# CAN-to-CAN.net
KiCad netlist of a schematic drawn in Altium Designer
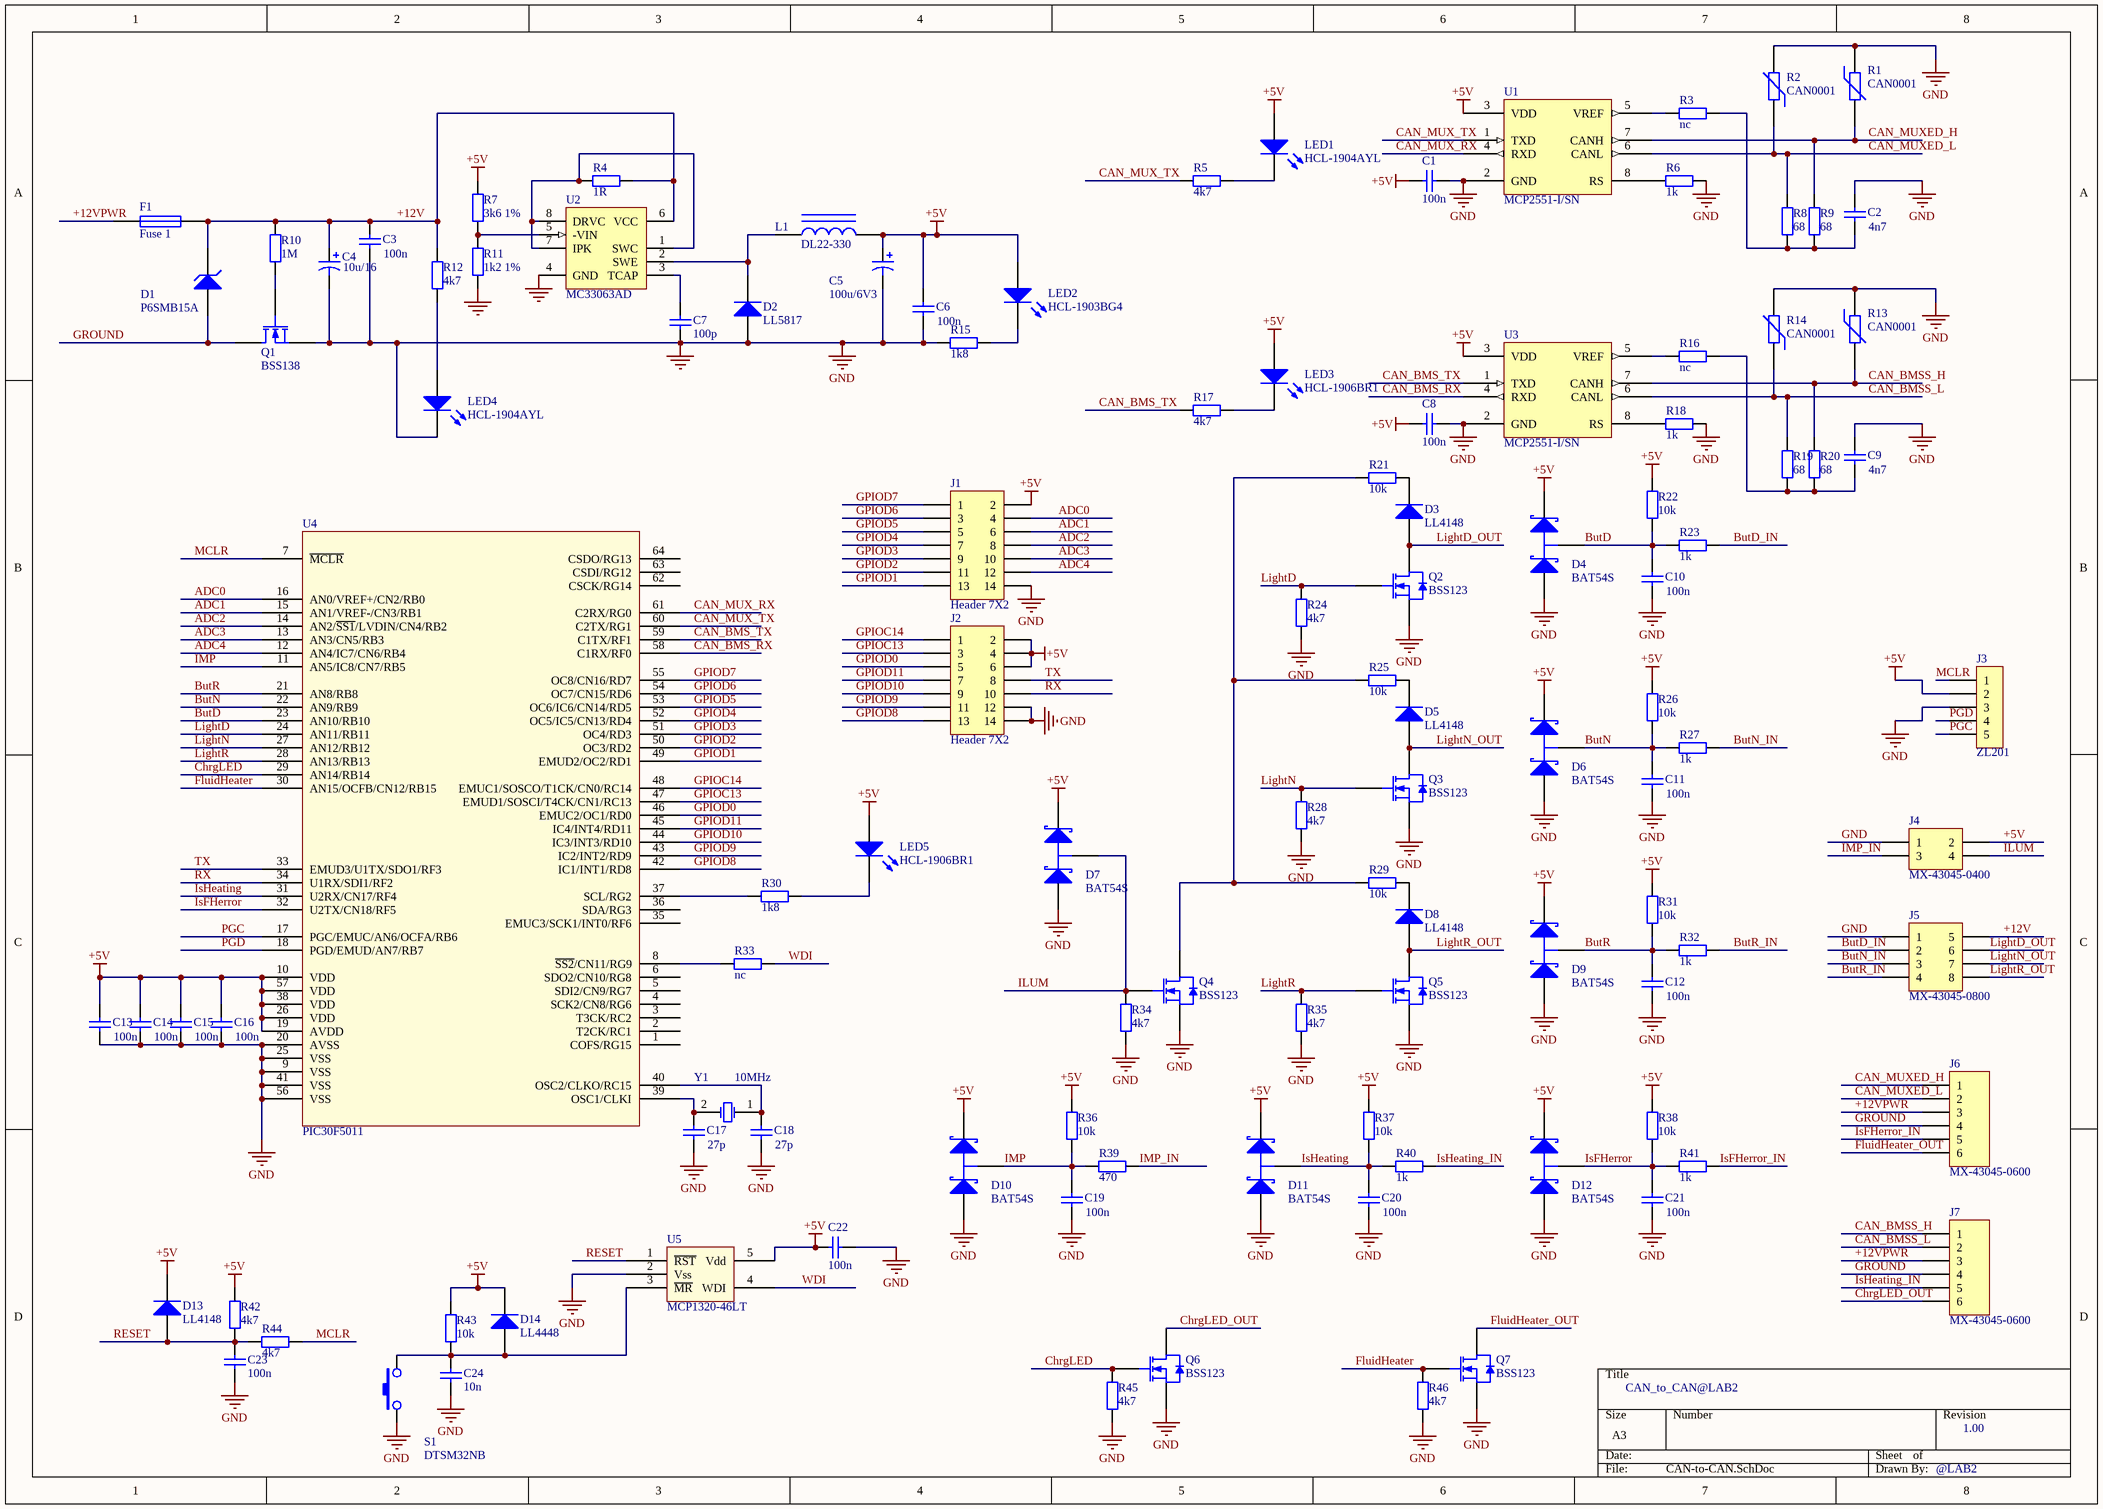
[diagram p0: CAN-to-CAN.SchDoc]

(export (version "E")
  (design (tool "Eeschema 10.0.6"))
  (components
    (comp (ref "C1")
      (value "100n")
      (footprint "0603")
      (description "Capacitor")
      (libsource (lib "Miscellaneous Devices") (part "Cap"))
    )
    (comp (ref "C2")
      (value "4n7")
      (footprint "0603")
      (description "Capacitor")
      (libsource (lib "Miscellaneous Devices") (part "Cap"))
    )
    (comp (ref "C3")
      (value "100n")
      (footprint "0402")
      (description "Capacitor")
      (libsource (lib "Miscellaneous Devices") (part "Cap"))
    )
    (comp (ref "C4")
      (value "10u/16")
      (footprint "0402")
      (description "Polarized Capacitor (Radial)")
      (libsource (lib "Miscellaneous Devices") (part "Cap Pol1"))
    )
    (comp (ref "C5")
      (value "100u/6V3")
      (footprint "0402")
      (description "Polarized Capacitor (Radial)")
      (libsource (lib "Miscellaneous Devices") (part "Cap Pol1"))
    )
    (comp (ref "C6")
      (value "100n")
      (footprint "0603")
      (description "Capacitor")
      (libsource (lib "Miscellaneous Devices") (part "Cap"))
    )
    (comp (ref "C7")
      (value "100p")
      (footprint "0603")
      (description "Capacitor")
      (libsource (lib "Miscellaneous Devices") (part "Cap"))
    )
    (comp (ref "C8")
      (value "100n")
      (footprint "0603")
      (description "Capacitor")
      (libsource (lib "Miscellaneous Devices") (part "Cap"))
    )
    (comp (ref "C9")
      (value "4n7")
      (footprint "0603")
      (description "Capacitor")
      (libsource (lib "Miscellaneous Devices") (part "Cap"))
    )
    (comp (ref "C10")
      (value "100n")
      (footprint "0603")
      (description "Capacitor")
      (libsource (lib "Miscellaneous Devices") (part "Cap"))
    )
    (comp (ref "C11")
      (value "100n")
      (footprint "0603")
      (description "Capacitor")
      (libsource (lib "Miscellaneous Devices") (part "Cap"))
    )
    (comp (ref "C12")
      (value "100n")
      (footprint "0603")
      (description "Capacitor")
      (libsource (lib "Miscellaneous Devices") (part "Cap"))
    )
    (comp (ref "C13")
      (value "100n")
      (footprint "0603")
      (description "Capacitor")
      (libsource (lib "Miscellaneous Devices") (part "Cap"))
    )
    (comp (ref "C14")
      (value "100n")
      (footprint "0603")
      (description "Capacitor")
      (libsource (lib "Miscellaneous Devices") (part "Cap"))
    )
    (comp (ref "C15")
      (value "100n")
      (footprint "0603")
      (description "Capacitor")
      (libsource (lib "Miscellaneous Devices") (part "Cap"))
    )
    (comp (ref "C16")
      (value "100n")
      (footprint "0603")
      (description "Capacitor")
      (libsource (lib "Miscellaneous Devices") (part "Cap"))
    )
    (comp (ref "C17")
      (value "27p")
      (footprint "0603")
      (description "Capacitor")
      (libsource (lib "Miscellaneous Devices") (part "Cap"))
    )
    (comp (ref "C18")
      (value "27p")
      (footprint "0603")
      (description "Capacitor")
      (libsource (lib "Miscellaneous Devices") (part "Cap"))
    )
    (comp (ref "C19")
      (value "100n")
      (footprint "0603")
      (description "Capacitor")
      (libsource (lib "Miscellaneous Devices") (part "Cap"))
    )
    (comp (ref "C20")
      (value "100n")
      (footprint "0603")
      (description "Capacitor")
      (libsource (lib "Miscellaneous Devices") (part "Cap"))
    )
    (comp (ref "C21")
      (value "100n")
      (footprint "0603")
      (description "Capacitor")
      (libsource (lib "Miscellaneous Devices") (part "Cap"))
    )
    (comp (ref "C22")
      (value "100n")
      (footprint "0603")
      (description "Capacitor")
      (libsource (lib "Miscellaneous Devices") (part "Cap"))
    )
    (comp (ref "C23")
      (value "100n")
      (footprint "0603")
      (description "Capacitor")
      (libsource (lib "Miscellaneous Devices") (part "Cap"))
    )
    (comp (ref "C24")
      (value "10n")
      (footprint "0603")
      (description "Capacitor")
      (libsource (lib "Miscellaneous Devices") (part "Cap"))
    )
    (comp (ref "D1")
      (value "P6SMB15A")
      (footprint "SMB")
      (description "Zener Diode")
      (libsource (lib "Miscellaneous Devices") (part "D Zener"))
    )
    (comp (ref "D2")
      (value "LL5817")
      (footprint "DIODE_SMC")
      (description "High Conductance Fast Diode")
      (libsource (lib "FSC Discrete Diode") (part "1N4148"))
    )
    (comp (ref "D3")
      (value "LL4148")
      (footprint "DIODE_SMC")
      (description "High Conductance Fast Diode")
      (libsource (lib "FSC Discrete Diode") (part "1N4148"))
    )
    (comp (ref "D4")
      (value "BAT54S")
      (footprint "SOT-23_M")
      (description "Schottky Barrier Double Diode")
      (libsource (lib "Philips Discrete Diode - Schottky") (part "BAT54S"))
    )
    (comp (ref "D5")
      (value "LL4148")
      (footprint "DIODE_SMC")
      (description "High Conductance Fast Diode")
      (libsource (lib "FSC Discrete Diode") (part "1N4148"))
    )
    (comp (ref "D6")
      (value "BAT54S")
      (footprint "SOT23_M")
      (description "Schottky Barrier Double Diode")
      (libsource (lib "Philips Discrete Diode - Schottky") (part "BAT54S"))
    )
    (comp (ref "D7")
      (value "BAT54S")
      (footprint "SOT23_M")
      (description "Schottky Barrier Double Diode")
      (libsource (lib "Philips Discrete Diode - Schottky") (part "BAT54S"))
    )
    (comp (ref "D8")
      (value "LL4148")
      (footprint "DIODE_SMC")
      (description "High Conductance Fast Diode")
      (libsource (lib "FSC Discrete Diode") (part "1N4148"))
    )
    (comp (ref "D9")
      (value "BAT54S")
      (footprint "SOT23_M")
      (description "Schottky Barrier Double Diode")
      (libsource (lib "Philips Discrete Diode - Schottky") (part "BAT54S"))
    )
    (comp (ref "D10")
      (value "BAT54S")
      (footprint "SOT23_M")
      (description "Schottky Barrier Double Diode")
      (libsource (lib "Philips Discrete Diode - Schottky") (part "BAT54S"))
    )
    (comp (ref "D11")
      (value "BAT54S")
      (footprint "SOT23_M")
      (description "Schottky Barrier Double Diode")
      (libsource (lib "Philips Discrete Diode - Schottky") (part "BAT54S"))
    )
    (comp (ref "D12")
      (value "BAT54S")
      (footprint "SOT23_M")
      (description "Schottky Barrier Double Diode")
      (libsource (lib "Philips Discrete Diode - Schottky") (part "BAT54S"))
    )
    (comp (ref "D13")
      (value "LL4148")
      (footprint "DIODE_SMC")
      (description "High Conductance Fast Diode")
      (libsource (lib "FSC Discrete Diode") (part "1N4148"))
    )
    (comp (ref "D14")
      (value "LL4448")
      (footprint "DIODE_SMC")
      (description "Default Diode")
      (libsource (lib "Miscellaneous Devices") (part "Diode"))
    )
    (comp (ref "F1")
      (value "Fuse 1")
      (footprint "1812")
      (description "Fuse")
      (libsource (lib "Miscellaneous Devices") (part "Fuse 1"))
    )
    (comp (ref "J1")
      (value "Header 7X2")
      (footprint "HDR2X7")
      (description "Header, 7-Pin, Dual row")
      (libsource (lib "Miscellaneous Connectors") (part "Header 7X2"))
    )
    (comp (ref "J2")
      (value "Header 7X2")
      (footprint "HDR2X7")
      (description "Header, 7-Pin, Dual row")
      (libsource (lib "Miscellaneous Connectors") (part "Header 7X2"))
    )
    (comp (ref "J3")
      (value "ZL201")
      (footprint "HDR1X5")
      (description "Connector")
      (libsource (lib "*") (part "CON5"))
    )
    (comp (ref "J4")
      (value "MX-43045-0400")
      (footprint "SOT-343_M")
      (description "Header, 2-Pin, Dual row")
      (libsource (lib "Miscellaneous Connectors") (part "Header 2X2"))
    )
    (comp (ref "J5")
      (value "MX-43045-0800")
      (footprint "DB008_M")
      (description "Header, 4-Pin, Dual row")
      (libsource (lib "Miscellaneous Connectors") (part "Header 4X2A"))
    )
    (comp (ref "J6")
      (value "MX-43045-0600")
      (footprint "Miscellaneous Connectors:HDR1X6")
      (description "Header, 6-Pin")
      (libsource (lib "Miscellaneous Connectors") (part "Header 6"))
    )
    (comp (ref "J7")
      (value "MX-43045-0600")
      (footprint "Miscellaneous Connectors:HDR1X6")
      (description "Header, 6-Pin")
      (libsource (lib "Miscellaneous Connectors") (part "Header 6"))
    )
    (comp (ref "L1")
      (value "DL22-330")
      (footprint "INDC1608L")
      (description "Magnetic-Core Inductor")
      (libsource (lib "Miscellaneous Devices") (part "Inductor Iron"))
    )
    (comp (ref "LED1")
      (value "HCL-1904AYL")
      (footprint "0603")
      (description "Typical BLUE SiC LED")
      (libsource (lib "Miscellaneous Devices") (part "LED3"))
    )
    (comp (ref "LED2")
      (value "HCL-1903BG4")
      (footprint "0603")
      (description "Typical BLUE SiC LED")
      (libsource (lib "Miscellaneous Devices") (part "LED3"))
    )
    (comp (ref "LED3")
      (value "HCL-1906BR1")
      (footprint "0603")
      (description "Typical BLUE SiC LED")
      (libsource (lib "Miscellaneous Devices") (part "LED3"))
    )
    (comp (ref "LED4")
      (value "HCL-1904AYL")
      (footprint "0603")
      (description "Typical BLUE SiC LED")
      (libsource (lib "Miscellaneous Devices") (part "LED3"))
    )
    (comp (ref "LED5")
      (value "HCL-1906BR1")
      (footprint "0603")
      (description "Typical BLUE SiC LED")
      (libsource (lib "Miscellaneous Devices") (part "LED3"))
    )
    (comp (ref "Q1")
      (value "BSS138")
      (footprint "SOT23_M")
      (description "N-Channel Enhancement Mode Vertical DMOS FET")
      (libsource (lib "Zetex Discrete MOSFET") (part "BSS138"))
    )
    (comp (ref "Q2")
      (value "BSS123")
      (footprint "SOT23_M")
      (description "N-channel Enhancement Mode Vertical D-MOSFET")
      (libsource (lib "Philips Discrete MOSFET - Low Power") (part "BSS123"))
    )
    (comp (ref "Q3")
      (value "BSS123")
      (footprint "SOT23_M")
      (description "N-channel Enhancement Mode Vertical D-MOSFET")
      (libsource (lib "Philips Discrete MOSFET - Low Power") (part "BSS123"))
    )
    (comp (ref "Q4")
      (value "BSS123")
      (footprint "SOT23_M")
      (description "N-channel Enhancement Mode Vertical D-MOSFET")
      (libsource (lib "Philips Discrete MOSFET - Low Power") (part "BSS123"))
    )
    (comp (ref "Q5")
      (value "BSS123")
      (footprint "SOT23_M")
      (description "N-channel Enhancement Mode Vertical D-MOSFET")
      (libsource (lib "Philips Discrete MOSFET - Low Power") (part "BSS123"))
    )
    (comp (ref "Q6")
      (value "BSS123")
      (footprint "SOT23_M")
      (description "N-channel Enhancement Mode Vertical D-MOSFET")
      (libsource (lib "Philips Discrete MOSFET - Low Power") (part "BSS123"))
    )
    (comp (ref "Q7")
      (value "BSS123")
      (footprint "SOT23_M")
      (description "N-channel Enhancement Mode Vertical D-MOSFET")
      (libsource (lib "Philips Discrete MOSFET - Low Power") (part "BSS123"))
    )
    (comp (ref "R1")
      (value "CAN0001")
      (footprint "0603")
      (description "Varistor (Voltage-Sensitive Resistor)")
      (libsource (lib "Miscellaneous Devices") (part "Res Varistor"))
    )
    (comp (ref "R2")
      (value "CAN0001")
      (footprint "0603")
      (description "Varistor (Voltage-Sensitive Resistor)")
      (libsource (lib "Miscellaneous Devices") (part "Res Varistor"))
    )
    (comp (ref "R3")
      (value "nc")
      (footprint "0603")
      (description "Resistor")
      (libsource (lib "") (part "Res2_1"))
    )
    (comp (ref "R4")
      (value "1R")
      (footprint "12Z-2010")
      (description "Resistor")
      (libsource (lib "") (part "Res2_1"))
    )
    (comp (ref "R5")
      (value "4k7")
      (footprint "0603")
      (description "Resistor")
      (libsource (lib "") (part "Res2_2"))
    )
    (comp (ref "R6")
      (value "1k")
      (footprint "0603")
      (description "Resistor")
      (libsource (lib "") (part "Res2_1"))
    )
    (comp (ref "R7")
      (value "3k6 1%")
      (footprint "0603")
      (description "Resistor")
      (libsource (lib "Miscellaneous Devices") (part "Res2"))
    )
    (comp (ref "R8")
      (value "68")
      (footprint "0603")
      (description "Resistor")
      (libsource (lib "Miscellaneous Devices") (part "Res2"))
    )
    (comp (ref "R9")
      (value "68")
      (footprint "0603")
      (description "Resistor")
      (libsource (lib "Miscellaneous Devices") (part "Res2"))
    )
    (comp (ref "R10")
      (value "1M")
      (footprint "0603")
      (description "Resistor")
      (libsource (lib "Miscellaneous Devices") (part "Res2"))
    )
    (comp (ref "R11")
      (value "1k2 1%")
      (footprint "0603")
      (description "Resistor")
      (libsource (lib "") (part "Res2_3"))
    )
    (comp (ref "R12")
      (value "4k7")
      (footprint "0603")
      (description "Resistor")
      (libsource (lib "Miscellaneous Devices") (part "Res2"))
    )
    (comp (ref "R13")
      (value "CAN0001")
      (footprint "0603")
      (description "Varistor (Voltage-Sensitive Resistor)")
      (libsource (lib "Miscellaneous Devices") (part "Res Varistor"))
    )
    (comp (ref "R14")
      (value "CAN0001")
      (footprint "0603")
      (description "Varistor (Voltage-Sensitive Resistor)")
      (libsource (lib "Miscellaneous Devices") (part "Res Varistor"))
    )
    (comp (ref "R15")
      (value "1k8")
      (footprint "0603")
      (description "Resistor")
      (libsource (lib "") (part "Res2_2"))
    )
    (comp (ref "R16")
      (value "nc")
      (footprint "0603")
      (description "Resistor")
      (libsource (lib "") (part "Res2_1"))
    )
    (comp (ref "R17")
      (value "4k7")
      (footprint "0603")
      (description "Resistor")
      (libsource (lib "") (part "Res2_2"))
    )
    (comp (ref "R18")
      (value "1k")
      (footprint "0603")
      (description "Resistor")
      (libsource (lib "") (part "Res2_1"))
    )
    (comp (ref "R19")
      (value "68")
      (footprint "0603")
      (description "Resistor")
      (libsource (lib "Miscellaneous Devices") (part "Res2"))
    )
    (comp (ref "R20")
      (value "68")
      (footprint "0603")
      (description "Resistor")
      (libsource (lib "Miscellaneous Devices") (part "Res2"))
    )
    (comp (ref "R21")
      (value "10k")
      (footprint "0603")
      (description "Resistor")
      (libsource (lib "") (part "Res2_1"))
    )
    (comp (ref "R22")
      (value "10k")
      (footprint "0603")
      (description "Resistor")
      (libsource (lib "Miscellaneous Devices") (part "Res2"))
    )
    (comp (ref "R23")
      (value "1k")
      (footprint "0603")
      (description "Resistor")
      (libsource (lib "") (part "Res2_2"))
    )
    (comp (ref "R24")
      (value "4k7")
      (footprint "0603")
      (description "Resistor")
      (libsource (lib "Miscellaneous Devices") (part "Res2"))
    )
    (comp (ref "R25")
      (value "10k")
      (footprint "0603")
      (description "Resistor")
      (libsource (lib "") (part "Res2_1"))
    )
    (comp (ref "R26")
      (value "10k")
      (footprint "0603")
      (description "Resistor")
      (libsource (lib "Miscellaneous Devices") (part "Res2"))
    )
    (comp (ref "R27")
      (value "1k")
      (footprint "0603")
      (description "Resistor")
      (libsource (lib "") (part "Res2_2"))
    )
    (comp (ref "R28")
      (value "4k7")
      (footprint "0603")
      (description "Resistor")
      (libsource (lib "Miscellaneous Devices") (part "Res2"))
    )
    (comp (ref "R29")
      (value "10k")
      (footprint "0603")
      (description "Resistor")
      (libsource (lib "") (part "Res2_1"))
    )
    (comp (ref "R30")
      (value "1k8")
      (footprint "0603")
      (description "Resistor")
      (libsource (lib "") (part "Res2_2"))
    )
    (comp (ref "R31")
      (value "10k")
      (footprint "0603")
      (description "Resistor")
      (libsource (lib "Miscellaneous Devices") (part "Res2"))
    )
    (comp (ref "R32")
      (value "1k")
      (footprint "0603")
      (description "Resistor")
      (libsource (lib "") (part "Res2_2"))
    )
    (comp (ref "R33")
      (value "nc")
      (footprint "0603")
      (description "Resistor")
      (libsource (lib "") (part "Res2_2"))
    )
    (comp (ref "R34")
      (value "4k7")
      (footprint "0603")
      (description "Resistor")
      (libsource (lib "Miscellaneous Devices") (part "Res2"))
    )
    (comp (ref "R35")
      (value "4k7")
      (footprint "0603")
      (description "Resistor")
      (libsource (lib "Miscellaneous Devices") (part "Res2"))
    )
    (comp (ref "R36")
      (value "10k")
      (footprint "0603")
      (description "Resistor")
      (libsource (lib "Miscellaneous Devices") (part "Res2"))
    )
    (comp (ref "R37")
      (value "10k")
      (footprint "0603")
      (description "Resistor")
      (libsource (lib "Miscellaneous Devices") (part "Res2"))
    )
    (comp (ref "R38")
      (value "10k")
      (footprint "0603")
      (description "Resistor")
      (libsource (lib "Miscellaneous Devices") (part "Res2"))
    )
    (comp (ref "R39")
      (value "470")
      (footprint "0603")
      (description "Resistor")
      (libsource (lib "") (part "Res2_2"))
    )
    (comp (ref "R40")
      (value "1k")
      (footprint "0603")
      (description "Resistor")
      (libsource (lib "") (part "Res2_2"))
    )
    (comp (ref "R41")
      (value "1k")
      (footprint "0603")
      (description "Resistor")
      (libsource (lib "") (part "Res2_2"))
    )
    (comp (ref "R42")
      (value "4k7")
      (footprint "0603")
      (description "Resistor")
      (libsource (lib "Miscellaneous Devices") (part "Res2"))
    )
    (comp (ref "R43")
      (value "10k")
      (footprint "0603")
      (description "Resistor")
      (libsource (lib "") (part "Res2_3"))
    )
    (comp (ref "R44")
      (value "4k7")
      (footprint "0603")
      (description "Resistor")
      (libsource (lib "") (part "Res2_2"))
    )
    (comp (ref "R45")
      (value "4k7")
      (footprint "0603")
      (description "Resistor")
      (libsource (lib "Miscellaneous Devices") (part "Res2"))
    )
    (comp (ref "R46")
      (value "4k7")
      (footprint "0603")
      (description "Resistor")
      (libsource (lib "Miscellaneous Devices") (part "Res2"))
    )
    (comp (ref "S1")
      (value "DTSM32NB")
      (footprint "SPST-2")
      (description "Switch PushButton")
      (libsource (lib "*") (part "PUSHB"))
    )
    (comp (ref "U1")
      (value "MCP2551-I/SN")
      (footprint "DB008_M")
      (description "High Speed CAN Transceiver, 8-Pin Plastic SOIC, Industrial Grade")
      (libsource (lib "Microchip Interface Line Transceiver") (part "MCP2551-I/SN"))
    )
    (comp (ref "U2")
      (value "MC33063AD")
      (footprint "SO8_N")
      (description "DC-to-DC Converter Control Circuit")
      (libsource (lib "Motorola Power Mgt DC-DC Converter") (part "MC33063AD"))
    )
    (comp (ref "U3")
      (value "MCP2551-I/SN")
      (footprint "M08A_L")
      (description "High Speed CAN Transceiver, 8-Pin Plastic SOIC, Industrial Grade")
      (libsource (lib "Microchip Interface Line Transceiver") (part "MCP2551-I/SN"))
    )
    (comp (ref "U4")
      (value "PIC30F5011")
      (footprint "RESC6332")
      (description "PIC30F5011 - Up")
      (libsource (lib "X-Tro's Misc") (part "PIC30F5011"))
    )
    (comp (ref "U5")
      (value "MCP1320-46LT")
      (footprint "SOT23-5")
      (libsource (lib "X-Tro's Misc") (part "MCP1320"))
    )
    (comp (ref "Y1")
      (value "10MHz")
      (footprint "XTALSMD2")
      (description "Crystal Oscillator")
      (libsource (lib "Miscellaneous Devices") (part "XTAL"))
    )
  )
  (nets
    (net (code "1") (name "+5V") (class "Default")
      (node (ref "C1") (pin "1") (pinfunction "1_1") (pintype "passive"))
      (node (ref "C13") (pin "1") (pinfunction "1_1") (pintype "passive"))
      (node (ref "C14") (pin "1") (pinfunction "1_1") (pintype "passive"))
      (node (ref "C15") (pin "1") (pinfunction "1_1") (pintype "passive"))
      (node (ref "C16") (pin "1") (pinfunction "1_1") (pintype "passive"))
      (node (ref "C22") (pin "1") (pinfunction "1_1") (pintype "passive"))
      (node (ref "C5") (pin "1") (pinfunction "1_1") (pintype "passive"))
      (node (ref "C6") (pin "1") (pinfunction "1_1") (pintype "passive"))
      (node (ref "C8") (pin "1") (pinfunction "1_1") (pintype "passive"))
      (node (ref "D10") (pin "2") (pinfunction "K_2") (pintype "passive"))
      (node (ref "D11") (pin "2") (pinfunction "K_2") (pintype "passive"))
      (node (ref "D12") (pin "2") (pinfunction "K_2") (pintype "passive"))
      (node (ref "D13") (pin "2") (pinfunction "K_2") (pintype "passive"))
      (node (ref "D14") (pin "2") (pinfunction "K_2") (pintype "passive"))
      (node (ref "D4") (pin "2") (pinfunction "K_2") (pintype "passive"))
      (node (ref "D6") (pin "2") (pinfunction "K_2") (pintype "passive"))
      (node (ref "D7") (pin "2") (pinfunction "K_2") (pintype "passive"))
      (node (ref "D9") (pin "2") (pinfunction "K_2") (pintype "passive"))
      (node (ref "J1") (pin "2") (pinfunction "2_2") (pintype "passive"))
      (node (ref "J2") (pin "2") (pinfunction "2_2") (pintype "passive"))
      (node (ref "J2") (pin "4") (pinfunction "4_4") (pintype "passive"))
      (node (ref "J2") (pin "6") (pinfunction "6_6") (pintype "passive"))
      (node (ref "J3") (pin "2") (pinfunction "2_2") (pintype "passive"))
      (node (ref "J4") (pin "2") (pinfunction "2_2") (pintype "passive"))
      (node (ref "L1") (pin "2") (pinfunction "2_2") (pintype "passive"))
      (node (ref "LED1") (pin "1") (pinfunction "A_1") (pintype "passive"))
      (node (ref "LED2") (pin "1") (pinfunction "A_1") (pintype "passive"))
      (node (ref "LED3") (pin "1") (pinfunction "A_1") (pintype "passive"))
      (node (ref "LED5") (pin "1") (pinfunction "A_1") (pintype "passive"))
      (node (ref "R22") (pin "1") (pinfunction "1_1") (pintype "passive"))
      (node (ref "R26") (pin "1") (pinfunction "1_1") (pintype "passive"))
      (node (ref "R31") (pin "1") (pinfunction "1_1") (pintype "passive"))
      (node (ref "R36") (pin "1") (pinfunction "1_1") (pintype "passive"))
      (node (ref "R37") (pin "1") (pinfunction "1_1") (pintype "passive"))
      (node (ref "R38") (pin "1") (pinfunction "1_1") (pintype "passive"))
      (node (ref "R42") (pin "1") (pinfunction "1_1") (pintype "passive"))
      (node (ref "R43") (pin "2") (pinfunction "2_2") (pintype "passive"))
      (node (ref "R7") (pin "1") (pinfunction "1_1") (pintype "passive"))
      (node (ref "U1") (pin "3") (pinfunction "VDD_3") (pintype "power_in"))
      (node (ref "U3") (pin "3") (pinfunction "VDD_3") (pintype "power_in"))
      (node (ref "U4") (pin "10") (pinfunction "VDD_10") (pintype "passive"))
      (node (ref "U4") (pin "19") (pinfunction "AVDD_19") (pintype "passive"))
      (node (ref "U4") (pin "26") (pinfunction "VDD_26") (pintype "passive"))
      (node (ref "U4") (pin "38") (pinfunction "VDD_38") (pintype "passive"))
      (node (ref "U4") (pin "57") (pinfunction "VDD_57") (pintype "passive"))
      (node (ref "U5") (pin "5") (pinfunction "Vdd_5") (pintype "passive"))
    )
    (net (code "2") (name "/+12V") (class "Default")
      (node (ref "C3") (pin "1") (pinfunction "1_1") (pintype "passive"))
      (node (ref "C4") (pin "1") (pinfunction "1_1") (pintype "passive"))
      (node (ref "D1") (pin "2") (pinfunction "K_2") (pintype "passive"))
      (node (ref "F1") (pin "2") (pinfunction "2_2") (pintype "passive"))
      (node (ref "J5") (pin "5") (pinfunction "5_5") (pintype "passive"))
      (node (ref "R10") (pin "1") (pinfunction "1_1") (pintype "passive"))
      (node (ref "R12") (pin "1") (pinfunction "1_1") (pintype "passive"))
      (node (ref "R4") (pin "2") (pinfunction "2_2") (pintype "passive"))
      (node (ref "U2") (pin "6") (pinfunction "VCC_6") (pintype "power_in"))
    )
    (net (code "3") (name "/+12VPWR") (class "Default")
      (node (ref "F1") (pin "1") (pinfunction "1_1") (pintype "passive"))
      (node (ref "J6") (pin "3") (pinfunction "3_3") (pintype "passive"))
      (node (ref "J7") (pin "3") (pinfunction "3_3") (pintype "passive"))
    )
    (net (code "4") (name "/ADC0") (class "Default")
      (node (ref "J1") (pin "4") (pinfunction "4_4") (pintype "passive"))
      (node (ref "U4") (pin "16") (pinfunction "AN0/VREF+/CN2/RB0_16") (pintype "passive"))
    )
    (net (code "5") (name "/ADC1") (class "Default")
      (node (ref "J1") (pin "6") (pinfunction "6_6") (pintype "passive"))
      (node (ref "U4") (pin "15") (pinfunction "AN1/VREF-/CN3/RB1_15") (pintype "passive"))
    )
    (net (code "6") (name "/ADC2") (class "Default")
      (node (ref "J1") (pin "8") (pinfunction "8_8") (pintype "passive"))
      (node (ref "U4") (pin "14") (pinfunction "AN2/~{SS1}/LVDIN/CN4/RB2_14") (pintype "passive"))
    )
    (net (code "7") (name "/ADC3") (class "Default")
      (node (ref "J1") (pin "10") (pinfunction "10_10") (pintype "passive"))
      (node (ref "U4") (pin "13") (pinfunction "AN3/CN5/RB3_13") (pintype "passive"))
    )
    (net (code "8") (name "/ADC4") (class "Default")
      (node (ref "J1") (pin "12") (pinfunction "12_12") (pintype "passive"))
      (node (ref "U4") (pin "12") (pinfunction "AN4/IC7/CN6/RB4_12") (pintype "passive"))
    )
    (net (code "9") (name "/ButD") (class "Default")
      (node (ref "C10") (pin "1") (pinfunction "1_1") (pintype "passive"))
      (node (ref "D4") (pin "3") (pinfunction "C_3") (pintype "passive"))
      (node (ref "R22") (pin "2") (pinfunction "2_2") (pintype "passive"))
      (node (ref "R23") (pin "2") (pinfunction "2_2") (pintype "passive"))
      (node (ref "U4") (pin "23") (pinfunction "AN10/RB10_23") (pintype "passive"))
    )
    (net (code "10") (name "/ButD_IN") (class "Default")
      (node (ref "J5") (pin "2") (pinfunction "2_2") (pintype "passive"))
      (node (ref "R23") (pin "1") (pinfunction "1_1") (pintype "passive"))
    )
    (net (code "11") (name "/ButN") (class "Default")
      (node (ref "C11") (pin "1") (pinfunction "1_1") (pintype "passive"))
      (node (ref "D6") (pin "3") (pinfunction "C_3") (pintype "passive"))
      (node (ref "R26") (pin "2") (pinfunction "2_2") (pintype "passive"))
      (node (ref "R27") (pin "2") (pinfunction "2_2") (pintype "passive"))
      (node (ref "U4") (pin "22") (pinfunction "AN9/RB9_22") (pintype "passive"))
    )
    (net (code "12") (name "/ButN_IN") (class "Default")
      (node (ref "J5") (pin "3") (pinfunction "3_3") (pintype "passive"))
      (node (ref "R27") (pin "1") (pinfunction "1_1") (pintype "passive"))
    )
    (net (code "13") (name "/ButR") (class "Default")
      (node (ref "C12") (pin "1") (pinfunction "1_1") (pintype "passive"))
      (node (ref "D9") (pin "3") (pinfunction "C_3") (pintype "passive"))
      (node (ref "R31") (pin "2") (pinfunction "2_2") (pintype "passive"))
      (node (ref "R32") (pin "2") (pinfunction "2_2") (pintype "passive"))
      (node (ref "U4") (pin "21") (pinfunction "AN8/RB8_21") (pintype "passive"))
    )
    (net (code "14") (name "/ButR_IN") (class "Default")
      (node (ref "J5") (pin "4") (pinfunction "4_4") (pintype "passive"))
      (node (ref "R32") (pin "1") (pinfunction "1_1") (pintype "passive"))
    )
    (net (code "15") (name "/CAN_BMSS_H") (class "Default")
      (node (ref "J7") (pin "1") (pinfunction "1_1") (pintype "passive"))
      (node (ref "R13") (pin "2") (pinfunction "2_2") (pintype "passive"))
      (node (ref "R20") (pin "1") (pinfunction "1_1") (pintype "passive"))
      (node (ref "U3") (pin "7") (pinfunction "CANH_7") (pintype "output"))
    )
    (net (code "16") (name "/CAN_BMSS_L") (class "Default")
      (node (ref "J7") (pin "2") (pinfunction "2_2") (pintype "passive"))
      (node (ref "R14") (pin "1") (pinfunction "1_1") (pintype "passive"))
      (node (ref "R19") (pin "1") (pinfunction "1_1") (pintype "passive"))
      (node (ref "U3") (pin "6") (pinfunction "CANL_6") (pintype "output"))
    )
    (net (code "17") (name "/CAN_BMS_RX") (class "Default")
      (node (ref "U3") (pin "4") (pinfunction "RXD_4") (pintype "output"))
      (node (ref "U4") (pin "58") (pinfunction "C1RX/RF0_58") (pintype "passive"))
    )
    (net (code "18") (name "/CAN_BMS_TX") (class "Default")
      (node (ref "R17") (pin "2") (pinfunction "2_2") (pintype "passive"))
      (node (ref "U3") (pin "1") (pinfunction "TXD_1") (pintype "input"))
      (node (ref "U4") (pin "59") (pinfunction "C1TX/RF1_59") (pintype "passive"))
    )
    (net (code "19") (name "/CAN_MUXED_H") (class "Default")
      (node (ref "J6") (pin "1") (pinfunction "1_1") (pintype "passive"))
      (node (ref "R1") (pin "2") (pinfunction "2_2") (pintype "passive"))
      (node (ref "R9") (pin "1") (pinfunction "1_1") (pintype "passive"))
      (node (ref "U1") (pin "7") (pinfunction "CANH_7") (pintype "output"))
    )
    (net (code "20") (name "/CAN_MUXED_L") (class "Default")
      (node (ref "J6") (pin "2") (pinfunction "2_2") (pintype "passive"))
      (node (ref "R2") (pin "1") (pinfunction "1_1") (pintype "passive"))
      (node (ref "R8") (pin "1") (pinfunction "1_1") (pintype "passive"))
      (node (ref "U1") (pin "6") (pinfunction "CANL_6") (pintype "output"))
    )
    (net (code "21") (name "/CAN_MUX_RX") (class "Default")
      (node (ref "U1") (pin "4") (pinfunction "RXD_4") (pintype "output"))
      (node (ref "U4") (pin "61") (pinfunction "C2RX/RG0_61") (pintype "passive"))
    )
    (net (code "22") (name "/CAN_MUX_TX") (class "Default")
      (node (ref "R5") (pin "2") (pinfunction "2_2") (pintype "passive"))
      (node (ref "U1") (pin "1") (pinfunction "TXD_1") (pintype "input"))
      (node (ref "U4") (pin "60") (pinfunction "C2TX/RG1_60") (pintype "passive"))
    )
    (net (code "23") (name "/ChrgLED") (class "Default")
      (node (ref "Q6") (pin "3") (pinfunction "G_3") (pintype "passive"))
      (node (ref "R45") (pin "1") (pinfunction "1_1") (pintype "passive"))
      (node (ref "U4") (pin "29") (pinfunction "AN14/RB14_29") (pintype "passive"))
    )
    (net (code "24") (name "/ChrgLED_OUT") (class "Default")
      (node (ref "J7") (pin "6") (pinfunction "6_6") (pintype "passive"))
      (node (ref "Q6") (pin "1") (pinfunction "D_1") (pintype "passive"))
    )
    (net (code "25") (name "/FluidHeater") (class "Default")
      (node (ref "Q7") (pin "3") (pinfunction "G_3") (pintype "passive"))
      (node (ref "R46") (pin "1") (pinfunction "1_1") (pintype "passive"))
      (node (ref "U4") (pin "30") (pinfunction "AN15/OCFB/CN12/RB15_30") (pintype "passive"))
    )
    (net (code "26") (name "/FluidHeater_OUT") (class "Default")
      (node (ref "J6") (pin "6") (pinfunction "6_6") (pintype "passive"))
      (node (ref "Q7") (pin "1") (pinfunction "D_1") (pintype "passive"))
    )
    (net (code "27") (name "/GPIOC13") (class "Default")
      (node (ref "J2") (pin "3") (pinfunction "3_3") (pintype "passive"))
      (node (ref "U4") (pin "47") (pinfunction "EMUD1/SOSCI/T4CK/CN1/RC13_47") (pintype "passive"))
    )
    (net (code "28") (name "/GPIOC14") (class "Default")
      (node (ref "J2") (pin "1") (pinfunction "1_1") (pintype "passive"))
      (node (ref "U4") (pin "48") (pinfunction "EMUC1/SOSCO/T1CK/CN0/RC14_48") (pintype "passive"))
    )
    (net (code "29") (name "/GPIOD0") (class "Default")
      (node (ref "J2") (pin "5") (pinfunction "5_5") (pintype "passive"))
      (node (ref "U4") (pin "46") (pinfunction "EMUC2/OC1/RD0_46") (pintype "passive"))
    )
    (net (code "30") (name "/GPIOD1") (class "Default")
      (node (ref "J1") (pin "13") (pinfunction "13_13") (pintype "passive"))
      (node (ref "U4") (pin "49") (pinfunction "EMUD2/OC2/RD1_49") (pintype "passive"))
    )
    (net (code "31") (name "/GPIOD2") (class "Default")
      (node (ref "J1") (pin "11") (pinfunction "11_11") (pintype "passive"))
      (node (ref "U4") (pin "50") (pinfunction "OC3/RD2_50") (pintype "passive"))
    )
    (net (code "32") (name "/GPIOD3") (class "Default")
      (node (ref "J1") (pin "9") (pinfunction "9_9") (pintype "passive"))
      (node (ref "U4") (pin "51") (pinfunction "OC4/RD3_51") (pintype "passive"))
    )
    (net (code "33") (name "/GPIOD4") (class "Default")
      (node (ref "J1") (pin "7") (pinfunction "7_7") (pintype "passive"))
      (node (ref "U4") (pin "52") (pinfunction "OC5/IC5/CN13/RD4_52") (pintype "passive"))
    )
    (net (code "34") (name "/GPIOD5") (class "Default")
      (node (ref "J1") (pin "5") (pinfunction "5_5") (pintype "passive"))
      (node (ref "U4") (pin "53") (pinfunction "OC6/IC6/CN14/RD5_53") (pintype "passive"))
    )
    (net (code "35") (name "/GPIOD6") (class "Default")
      (node (ref "J1") (pin "3") (pinfunction "3_3") (pintype "passive"))
      (node (ref "U4") (pin "54") (pinfunction "OC7/CN15/RD6_54") (pintype "passive"))
    )
    (net (code "36") (name "/GPIOD7") (class "Default")
      (node (ref "J1") (pin "1") (pinfunction "1_1") (pintype "passive"))
      (node (ref "U4") (pin "55") (pinfunction "OC8/CN16/RD7_55") (pintype "passive"))
    )
    (net (code "37") (name "/GPIOD8") (class "Default")
      (node (ref "J2") (pin "13") (pinfunction "13_13") (pintype "passive"))
      (node (ref "U4") (pin "42") (pinfunction "IC1/INT1/RD8_42") (pintype "passive"))
    )
    (net (code "38") (name "/GPIOD9") (class "Default")
      (node (ref "J2") (pin "11") (pinfunction "11_11") (pintype "passive"))
      (node (ref "U4") (pin "43") (pinfunction "IC2/INT2/RD9_43") (pintype "passive"))
    )
    (net (code "39") (name "/GPIOD10") (class "Default")
      (node (ref "J2") (pin "9") (pinfunction "9_9") (pintype "passive"))
      (node (ref "U4") (pin "44") (pinfunction "IC3/INT3/RD10_44") (pintype "passive"))
    )
    (net (code "40") (name "/GPIOD11") (class "Default")
      (node (ref "J2") (pin "7") (pinfunction "7_7") (pintype "passive"))
      (node (ref "U4") (pin "45") (pinfunction "IC4/INT4/RD11_45") (pintype "passive"))
    )
    (net (code "41") (name "/GROUND") (class "Default")
      (node (ref "D1") (pin "1") (pinfunction "A_1") (pintype "passive"))
      (node (ref "J6") (pin "4") (pinfunction "4_4") (pintype "passive"))
      (node (ref "J7") (pin "4") (pinfunction "4_4") (pintype "passive"))
      (node (ref "Q1") (pin "1") (pinfunction "D_1") (pintype "passive"))
    )
    (net (code "42") (name "/ILUM") (class "Default")
      (node (ref "D7") (pin "3") (pinfunction "C_3") (pintype "passive"))
      (node (ref "J4") (pin "4") (pinfunction "4_4") (pintype "passive"))
      (node (ref "Q4") (pin "3") (pinfunction "G_3") (pintype "passive"))
      (node (ref "R34") (pin "1") (pinfunction "1_1") (pintype "passive"))
    )
    (net (code "43") (name "/IMP") (class "Default")
      (node (ref "C19") (pin "1") (pinfunction "1_1") (pintype "passive"))
      (node (ref "D10") (pin "3") (pinfunction "C_3") (pintype "passive"))
      (node (ref "R36") (pin "2") (pinfunction "2_2") (pintype "passive"))
      (node (ref "R39") (pin "2") (pinfunction "2_2") (pintype "passive"))
      (node (ref "U4") (pin "11") (pinfunction "AN5/IC8/CN7/RB5_11") (pintype "passive"))
    )
    (net (code "44") (name "/IMP_IN") (class "Default")
      (node (ref "J4") (pin "3") (pinfunction "3_3") (pintype "passive"))
      (node (ref "R39") (pin "1") (pinfunction "1_1") (pintype "passive"))
    )
    (net (code "45") (name "/IsFHerror") (class "Default")
      (node (ref "C21") (pin "1") (pinfunction "1_1") (pintype "passive"))
      (node (ref "D12") (pin "3") (pinfunction "C_3") (pintype "passive"))
      (node (ref "R38") (pin "2") (pinfunction "2_2") (pintype "passive"))
      (node (ref "R41") (pin "2") (pinfunction "2_2") (pintype "passive"))
      (node (ref "U4") (pin "32") (pinfunction "U2TX/CN18/RF5_32") (pintype "passive"))
    )
    (net (code "46") (name "/IsFHerror_IN") (class "Default")
      (node (ref "J6") (pin "5") (pinfunction "5_5") (pintype "passive"))
      (node (ref "R41") (pin "1") (pinfunction "1_1") (pintype "passive"))
    )
    (net (code "47") (name "/IsHeating") (class "Default")
      (node (ref "C20") (pin "1") (pinfunction "1_1") (pintype "passive"))
      (node (ref "D11") (pin "3") (pinfunction "C_3") (pintype "passive"))
      (node (ref "R37") (pin "2") (pinfunction "2_2") (pintype "passive"))
      (node (ref "R40") (pin "2") (pinfunction "2_2") (pintype "passive"))
      (node (ref "U4") (pin "31") (pinfunction "U2RX/CN17/RF4_31") (pintype "passive"))
    )
    (net (code "48") (name "/IsHeating_IN") (class "Default")
      (node (ref "J7") (pin "5") (pinfunction "5_5") (pintype "passive"))
      (node (ref "R40") (pin "1") (pinfunction "1_1") (pintype "passive"))
    )
    (net (code "49") (name "/LightD") (class "Default")
      (node (ref "Q2") (pin "3") (pinfunction "G_3") (pintype "passive"))
      (node (ref "R24") (pin "1") (pinfunction "1_1") (pintype "passive"))
      (node (ref "U4") (pin "24") (pinfunction "AN11/RB11_24") (pintype "passive"))
    )
    (net (code "50") (name "/LightD_OUT") (class "Default")
      (node (ref "D3") (pin "1") (pinfunction "A_1") (pintype "passive"))
      (node (ref "J5") (pin "6") (pinfunction "6_6") (pintype "passive"))
      (node (ref "Q2") (pin "1") (pinfunction "D_1") (pintype "passive"))
    )
    (net (code "51") (name "/LightN") (class "Default")
      (node (ref "Q3") (pin "3") (pinfunction "G_3") (pintype "passive"))
      (node (ref "R28") (pin "1") (pinfunction "1_1") (pintype "passive"))
      (node (ref "U4") (pin "27") (pinfunction "AN12/RB12_27") (pintype "passive"))
    )
    (net (code "52") (name "/LightN_OUT") (class "Default")
      (node (ref "D5") (pin "1") (pinfunction "A_1") (pintype "passive"))
      (node (ref "J5") (pin "7") (pinfunction "7_7") (pintype "passive"))
      (node (ref "Q3") (pin "1") (pinfunction "D_1") (pintype "passive"))
    )
    (net (code "53") (name "/LightR") (class "Default")
      (node (ref "Q5") (pin "3") (pinfunction "G_3") (pintype "passive"))
      (node (ref "R35") (pin "1") (pinfunction "1_1") (pintype "passive"))
      (node (ref "U4") (pin "28") (pinfunction "AN13/RB13_28") (pintype "passive"))
    )
    (net (code "54") (name "/LightR_OUT") (class "Default")
      (node (ref "D8") (pin "1") (pinfunction "A_1") (pintype "passive"))
      (node (ref "J5") (pin "8") (pinfunction "8_8") (pintype "passive"))
      (node (ref "Q5") (pin "1") (pinfunction "D_1") (pintype "passive"))
    )
    (net (code "55") (name "/MCLR") (class "Default")
      (node (ref "J3") (pin "1") (pinfunction "1_1") (pintype "passive"))
      (node (ref "R44") (pin "1") (pinfunction "1_1") (pintype "passive"))
      (node (ref "U4") (pin "7") (pinfunction "~{MCLR}_7") (pintype "passive"))
    )
    (net (code "56") (name "/PGC") (class "Default")
      (node (ref "J3") (pin "5") (pinfunction "5_5") (pintype "passive"))
      (node (ref "U4") (pin "17") (pinfunction "PGC/EMUC/AN6/OCFA/RB6_17") (pintype "passive"))
    )
    (net (code "57") (name "/PGD") (class "Default")
      (node (ref "J3") (pin "4") (pinfunction "4_4") (pintype "passive"))
      (node (ref "U4") (pin "18") (pinfunction "PGD/EMUD/AN7/RB7_18") (pintype "passive"))
    )
    (net (code "58") (name "/RESET") (class "Default")
      (node (ref "C23") (pin "2") (pinfunction "2_2") (pintype "passive"))
      (node (ref "D13") (pin "1") (pinfunction "A_1") (pintype "passive"))
      (node (ref "R42") (pin "2") (pinfunction "2_2") (pintype "passive"))
      (node (ref "R44") (pin "2") (pinfunction "2_2") (pintype "passive"))
      (node (ref "U5") (pin "1") (pinfunction "~{RST}_1") (pintype "passive"))
    )
    (net (code "59") (name "/RX") (class "Default")
      (node (ref "J2") (pin "10") (pinfunction "10_10") (pintype "passive"))
      (node (ref "U4") (pin "34") (pinfunction "U1RX/SDI1/RF2_34") (pintype "passive"))
    )
    (net (code "60") (name "/TX") (class "Default")
      (node (ref "J2") (pin "8") (pinfunction "8_8") (pintype "passive"))
      (node (ref "U4") (pin "33") (pinfunction "EMUD3/U1TX/SDO1/RF3_33") (pintype "passive"))
    )
    (net (code "61") (name "/WDI") (class "Default")
      (node (ref "R33") (pin "1") (pinfunction "1_1") (pintype "passive"))
      (node (ref "U5") (pin "4") (pinfunction "WDI_4") (pintype "passive"))
    )
    (net (code "62") (name "GND") (class "Default")
      (node (ref "C1") (pin "2") (pinfunction "2_2") (pintype "passive"))
      (node (ref "C10") (pin "2") (pinfunction "2_2") (pintype "passive"))
      (node (ref "C11") (pin "2") (pinfunction "2_2") (pintype "passive"))
      (node (ref "C12") (pin "2") (pinfunction "2_2") (pintype "passive"))
      (node (ref "C13") (pin "2") (pinfunction "2_2") (pintype "passive"))
      (node (ref "C14") (pin "2") (pinfunction "2_2") (pintype "passive"))
      (node (ref "C15") (pin "2") (pinfunction "2_2") (pintype "passive"))
      (node (ref "C16") (pin "2") (pinfunction "2_2") (pintype "passive"))
      (node (ref "C17") (pin "2") (pinfunction "2_2") (pintype "passive"))
      (node (ref "C18") (pin "2") (pinfunction "2_2") (pintype "passive"))
      (node (ref "C19") (pin "2") (pinfunction "2_2") (pintype "passive"))
      (node (ref "C2") (pin "1") (pinfunction "1_1") (pintype "passive"))
      (node (ref "C20") (pin "2") (pinfunction "2_2") (pintype "passive"))
      (node (ref "C21") (pin "2") (pinfunction "2_2") (pintype "passive"))
      (node (ref "C22") (pin "2") (pinfunction "2_2") (pintype "passive"))
      (node (ref "C23") (pin "1") (pinfunction "1_1") (pintype "passive"))
      (node (ref "C24") (pin "1") (pinfunction "1_1") (pintype "passive"))
      (node (ref "C3") (pin "2") (pinfunction "2_2") (pintype "passive"))
      (node (ref "C4") (pin "2") (pinfunction "2_2") (pintype "passive"))
      (node (ref "C5") (pin "2") (pinfunction "2_2") (pintype "passive"))
      (node (ref "C6") (pin "2") (pinfunction "2_2") (pintype "passive"))
      (node (ref "C7") (pin "1") (pinfunction "1_1") (pintype "passive"))
      (node (ref "C8") (pin "2") (pinfunction "2_2") (pintype "passive"))
      (node (ref "C9") (pin "1") (pinfunction "1_1") (pintype "passive"))
      (node (ref "D10") (pin "1") (pinfunction "A_1") (pintype "passive"))
      (node (ref "D11") (pin "1") (pinfunction "A_1") (pintype "passive"))
      (node (ref "D12") (pin "1") (pinfunction "A_1") (pintype "passive"))
      (node (ref "D2") (pin "1") (pinfunction "A_1") (pintype "passive"))
      (node (ref "D4") (pin "1") (pinfunction "A_1") (pintype "passive"))
      (node (ref "D6") (pin "1") (pinfunction "A_1") (pintype "passive"))
      (node (ref "D7") (pin "1") (pinfunction "A_1") (pintype "passive"))
      (node (ref "D9") (pin "1") (pinfunction "A_1") (pintype "passive"))
      (node (ref "J1") (pin "14") (pinfunction "14_14") (pintype "passive"))
      (node (ref "J2") (pin "12") (pinfunction "12_12") (pintype "passive"))
      (node (ref "J2") (pin "14") (pinfunction "14_14") (pintype "passive"))
      (node (ref "J3") (pin "3") (pinfunction "3_3") (pintype "passive"))
      (node (ref "J4") (pin "1") (pinfunction "1_1") (pintype "passive"))
      (node (ref "J5") (pin "1") (pinfunction "1_1") (pintype "passive"))
      (node (ref "LED4") (pin "2") (pinfunction "K_2") (pintype "passive"))
      (node (ref "Q1") (pin "2") (pinfunction "S_2") (pintype "passive"))
      (node (ref "Q2") (pin "2") (pinfunction "S_2") (pintype "passive"))
      (node (ref "Q3") (pin "2") (pinfunction "S_2") (pintype "passive"))
      (node (ref "Q4") (pin "2") (pinfunction "S_2") (pintype "passive"))
      (node (ref "Q5") (pin "2") (pinfunction "S_2") (pintype "passive"))
      (node (ref "Q6") (pin "2") (pinfunction "S_2") (pintype "passive"))
      (node (ref "Q7") (pin "2") (pinfunction "S_2") (pintype "passive"))
      (node (ref "R1") (pin "1") (pinfunction "1_1") (pintype "passive"))
      (node (ref "R11") (pin "1") (pinfunction "1_1") (pintype "passive"))
      (node (ref "R13") (pin "1") (pinfunction "1_1") (pintype "passive"))
      (node (ref "R14") (pin "2") (pinfunction "2_2") (pintype "passive"))
      (node (ref "R15") (pin "2") (pinfunction "2_2") (pintype "passive"))
      (node (ref "R18") (pin "2") (pinfunction "2_2") (pintype "passive"))
      (node (ref "R2") (pin "2") (pinfunction "2_2") (pintype "passive"))
      (node (ref "R24") (pin "2") (pinfunction "2_2") (pintype "passive"))
      (node (ref "R28") (pin "2") (pinfunction "2_2") (pintype "passive"))
      (node (ref "R34") (pin "2") (pinfunction "2_2") (pintype "passive"))
      (node (ref "R35") (pin "2") (pinfunction "2_2") (pintype "passive"))
      (node (ref "R45") (pin "2") (pinfunction "2_2") (pintype "passive"))
      (node (ref "R46") (pin "2") (pinfunction "2_2") (pintype "passive"))
      (node (ref "R6") (pin "2") (pinfunction "2_2") (pintype "passive"))
      (node (ref "S1") (pin "1") (pintype "passive"))
      (node (ref "U1") (pin "2") (pinfunction "GND_2") (pintype "power_in"))
      (node (ref "U2") (pin "4") (pinfunction "GND_4") (pintype "power_in"))
      (node (ref "U3") (pin "2") (pinfunction "GND_2") (pintype "power_in"))
      (node (ref "U4") (pin "20") (pinfunction "AVSS_20") (pintype "passive"))
      (node (ref "U4") (pin "25") (pinfunction "VSS_25") (pintype "passive"))
      (node (ref "U4") (pin "41") (pinfunction "VSS_41") (pintype "passive"))
      (node (ref "U4") (pin "56") (pinfunction "VSS_56") (pintype "passive"))
      (node (ref "U4") (pin "9") (pinfunction "VSS_9") (pintype "passive"))
      (node (ref "U5") (pin "2") (pinfunction "Vss_2") (pintype "passive"))
    )
    (net (code "63") (name "Net-(C2-Pad2)") (class "Default")
      (node (ref "C2") (pin "2") (pinfunction "2_2") (pintype "passive"))
      (node (ref "R3") (pin "2") (pinfunction "2_2") (pintype "passive"))
      (node (ref "R8") (pin "2") (pinfunction "2_2") (pintype "passive"))
      (node (ref "R9") (pin "2") (pinfunction "2_2") (pintype "passive"))
    )
    (net (code "64") (name "Net-(C9-Pad2)") (class "Default")
      (node (ref "C9") (pin "2") (pinfunction "2_2") (pintype "passive"))
      (node (ref "R16") (pin "2") (pinfunction "2_2") (pintype "passive"))
      (node (ref "R19") (pin "2") (pinfunction "2_2") (pintype "passive"))
      (node (ref "R20") (pin "2") (pinfunction "2_2") (pintype "passive"))
    )
    (net (code "65") (name "Net-(D2-K)") (class "Default")
      (node (ref "D2") (pin "2") (pinfunction "K_2") (pintype "passive"))
      (node (ref "L1") (pin "1") (pinfunction "1_1") (pintype "passive"))
      (node (ref "U2") (pin "2") (pinfunction "SWE_2") (pintype "open_emitter"))
    )
    (net (code "66") (name "Net-(D3-K)") (class "Default")
      (node (ref "D3") (pin "2") (pinfunction "K_2") (pintype "passive"))
      (node (ref "R21") (pin "2") (pinfunction "2_2") (pintype "passive"))
    )
    (net (code "67") (name "Net-(D5-K)") (class "Default")
      (node (ref "D5") (pin "2") (pinfunction "K_2") (pintype "passive"))
      (node (ref "R25") (pin "2") (pinfunction "2_2") (pintype "passive"))
    )
    (net (code "68") (name "Net-(D8-K)") (class "Default")
      (node (ref "D8") (pin "2") (pinfunction "K_2") (pintype "passive"))
      (node (ref "R29") (pin "2") (pinfunction "2_2") (pintype "passive"))
    )
    (net (code "69") (name "Net-(D14-A)") (class "Default")
      (node (ref "C24") (pin "2") (pinfunction "2_2") (pintype "passive"))
      (node (ref "D14") (pin "1") (pinfunction "A_1") (pintype "passive"))
      (node (ref "R43") (pin "1") (pinfunction "1_1") (pintype "passive"))
      (node (ref "S1") (pin "2") (pintype "passive"))
      (node (ref "U5") (pin "3") (pinfunction "~{MR}_3") (pintype "passive"))
    )
    (net (code "70") (name "Net-(LED1-K)") (class "Default")
      (node (ref "LED1") (pin "2") (pinfunction "K_2") (pintype "passive"))
      (node (ref "R5") (pin "1") (pinfunction "1_1") (pintype "passive"))
    )
    (net (code "71") (name "Net-(LED2-K)") (class "Default")
      (node (ref "LED2") (pin "2") (pinfunction "K_2") (pintype "passive"))
      (node (ref "R15") (pin "1") (pinfunction "1_1") (pintype "passive"))
    )
    (net (code "72") (name "Net-(LED3-K)") (class "Default")
      (node (ref "LED3") (pin "2") (pinfunction "K_2") (pintype "passive"))
      (node (ref "R17") (pin "1") (pinfunction "1_1") (pintype "passive"))
    )
    (net (code "73") (name "Net-(LED4-A)") (class "Default")
      (node (ref "LED4") (pin "1") (pinfunction "A_1") (pintype "passive"))
      (node (ref "R12") (pin "2") (pinfunction "2_2") (pintype "passive"))
    )
    (net (code "74") (name "Net-(LED5-K)") (class "Default")
      (node (ref "LED5") (pin "2") (pinfunction "K_2") (pintype "passive"))
      (node (ref "R30") (pin "1") (pinfunction "1_1") (pintype "passive"))
    )
    (net (code "75") (name "Net-(Q1-G)") (class "Default")
      (node (ref "Q1") (pin "3") (pinfunction "G_3") (pintype "passive"))
      (node (ref "R10") (pin "2") (pinfunction "2_2") (pintype "passive"))
    )
    (net (code "76") (name "Net-(Q4-D)") (class "Default")
      (node (ref "Q4") (pin "1") (pinfunction "D_1") (pintype "passive"))
      (node (ref "R21") (pin "1") (pinfunction "1_1") (pintype "passive"))
      (node (ref "R25") (pin "1") (pinfunction "1_1") (pintype "passive"))
      (node (ref "R29") (pin "1") (pinfunction "1_1") (pintype "passive"))
    )
    (net (code "77") (name "Net-(U1-RS)") (class "Default")
      (node (ref "R6") (pin "1") (pinfunction "1_1") (pintype "passive"))
      (node (ref "U1") (pin "8") (pinfunction "RS_8") (pintype "passive"))
    )
    (net (code "78") (name "Net-(U1-VREF)") (class "Default")
      (node (ref "R3") (pin "1") (pinfunction "1_1") (pintype "passive"))
      (node (ref "U1") (pin "5") (pinfunction "VREF_5") (pintype "output"))
    )
    (net (code "79") (name "Net-(U2--VIN)") (class "Default")
      (node (ref "R11") (pin "2") (pinfunction "2_2") (pintype "passive"))
      (node (ref "R7") (pin "2") (pinfunction "2_2") (pintype "passive"))
      (node (ref "U2") (pin "5") (pinfunction "-VIN_5") (pintype "input"))
    )
    (net (code "80") (name "Net-(U2-DRVC)") (class "Default")
      (node (ref "R4") (pin "1") (pinfunction "1_1") (pintype "passive"))
      (node (ref "U2") (pin "1") (pinfunction "SWC_1") (pintype "open_collector"))
      (node (ref "U2") (pin "7") (pinfunction "IPK_7") (pintype "passive"))
      (node (ref "U2") (pin "8") (pinfunction "DRVC_8") (pintype "open_collector"))
    )
    (net (code "81") (name "Net-(U2-TCAP)") (class "Default")
      (node (ref "C7") (pin "2") (pinfunction "2_2") (pintype "passive"))
      (node (ref "U2") (pin "3") (pinfunction "TCAP_3") (pintype "passive"))
    )
    (net (code "82") (name "Net-(U3-RS)") (class "Default")
      (node (ref "R18") (pin "1") (pinfunction "1_1") (pintype "passive"))
      (node (ref "U3") (pin "8") (pinfunction "RS_8") (pintype "passive"))
    )
    (net (code "83") (name "Net-(U3-VREF)") (class "Default")
      (node (ref "R16") (pin "1") (pinfunction "1_1") (pintype "passive"))
      (node (ref "U3") (pin "5") (pinfunction "VREF_5") (pintype "output"))
    )
    (net (code "84") (name "Net-(U4-OSC1{slash}CLKI)") (class "Default")
      (node (ref "C17") (pin "1") (pinfunction "1_1") (pintype "passive"))
      (node (ref "U4") (pin "39") (pinfunction "OSC1/CLKI_39") (pintype "passive"))
      (node (ref "Y1") (pin "2") (pinfunction "OSC2_2") (pintype "passive"))
    )
    (net (code "85") (name "Net-(U4-OSC2{slash}CLKO{slash}RC15)") (class "Default")
      (node (ref "C18") (pin "1") (pinfunction "1_1") (pintype "passive"))
      (node (ref "U4") (pin "40") (pinfunction "OSC2/CLKO/RC15_40") (pintype "passive"))
      (node (ref "Y1") (pin "1") (pinfunction "OSC1_1") (pintype "passive"))
    )
    (net (code "86") (name "Net-(U4-SCL{slash}RG2)") (class "Default")
      (node (ref "R30") (pin "2") (pinfunction "2_2") (pintype "passive"))
      (node (ref "U4") (pin "37") (pinfunction "SCL/RG2_37") (pintype "passive"))
    )
    (net (code "87") (name "Net-(U4-~{SS2}{slash}CN11{slash}RG9)") (class "Default")
      (node (ref "R33") (pin "2") (pinfunction "2_2") (pintype "passive"))
      (node (ref "U4") (pin "8") (pinfunction "~{SS2}/CN11/RG9_8") (pintype "passive"))
    )
    (net (code "88") (name "unconnected-(U4-COFS{slash}RG15-Pad1)") (class "Default")
      (node (ref "U4") (pin "1") (pinfunction "COFS/RG15_1") (pintype "passive"))
    )
    (net (code "89") (name "unconnected-(U4-CSCK{slash}RG14-Pad62)") (class "Default")
      (node (ref "U4") (pin "62") (pinfunction "CSCK/RG14_62") (pintype "passive"))
    )
    (net (code "90") (name "unconnected-(U4-CSDI{slash}RG12-Pad63)") (class "Default")
      (node (ref "U4") (pin "63") (pinfunction "CSDI/RG12_63") (pintype "passive"))
    )
    (net (code "91") (name "unconnected-(U4-CSDO{slash}RG13-Pad64)") (class "Default")
      (node (ref "U4") (pin "64") (pinfunction "CSDO/RG13_64") (pintype "passive"))
    )
    (net (code "92") (name "unconnected-(U4-EMUC3{slash}SCK1{slash}INT0{slash}RF6-Pad35)") (class "Default")
      (node (ref "U4") (pin "35") (pinfunction "EMUC3/SCK1/INT0/RF6_35") (pintype "passive"))
    )
    (net (code "93") (name "unconnected-(U4-SCK2{slash}CN8{slash}RG6-Pad4)") (class "Default")
      (node (ref "U4") (pin "4") (pinfunction "SCK2/CN8/RG6_4") (pintype "passive"))
    )
    (net (code "94") (name "unconnected-(U4-SDA{slash}RG3-Pad36)") (class "Default")
      (node (ref "U4") (pin "36") (pinfunction "SDA/RG3_36") (pintype "passive"))
    )
    (net (code "95") (name "unconnected-(U4-SDI2{slash}CN9{slash}RG7-Pad5)") (class "Default")
      (node (ref "U4") (pin "5") (pinfunction "SDI2/CN9/RG7_5") (pintype "passive"))
    )
    (net (code "96") (name "unconnected-(U4-SDO2{slash}CN10{slash}RG8-Pad6)") (class "Default")
      (node (ref "U4") (pin "6") (pinfunction "SDO2/CN10/RG8_6") (pintype "passive"))
    )
    (net (code "97") (name "unconnected-(U4-T2CK{slash}RC1-Pad2)") (class "Default")
      (node (ref "U4") (pin "2") (pinfunction "T2CK/RC1_2") (pintype "passive"))
    )
    (net (code "98") (name "unconnected-(U4-T3CK{slash}RC2-Pad3)") (class "Default")
      (node (ref "U4") (pin "3") (pinfunction "T3CK/RC2_3") (pintype "passive"))
    )
  )
)
